# LEDStrips.net
KiCad netlist of a schematic drawn in Altium Designer
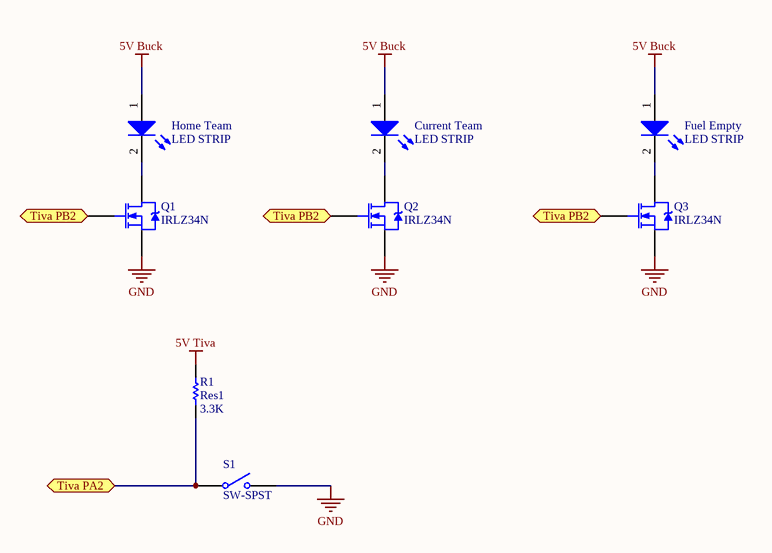
[diagram p0: LEDStrips.SchDoc]

(export (version "E")
  (design (tool "Eeschema 10.0.6"))
  (components
    (comp (ref "Current Team")
      (value "LED STRIP")
      (footprint "LED-0")
      (description "Typical INFRARED GaAs LED")
      (fields
        (field (name "MANUFACTURER") "Generic Components")
        (field (name "PUBLISHER") "Altium Hobart Technology Centre")
      )
      (libsource (lib "ME218_BaseLib") (part "LED0"))
    )
    (comp (ref "Fuel Empty")
      (value "LED STRIP")
      (footprint "LED-0")
      (description "Typical INFRARED GaAs LED")
      (fields
        (field (name "MANUFACTURER") "Generic Components")
        (field (name "PUBLISHER") "Altium Hobart Technology Centre")
      )
      (libsource (lib "ME218_BaseLib") (part "LED0"))
    )
    (comp (ref "Home Team")
      (value "LED STRIP")
      (footprint "LED-0")
      (description "Typical INFRARED GaAs LED")
      (fields
        (field (name "MANUFACTURER") "Generic Components")
        (field (name "PUBLISHER") "Altium Hobart Technology Centre")
      )
      (libsource (lib "ME218_BaseLib") (part "LED0"))
    )
    (comp (ref "Q1")
      (value "IRLZ34N")
      (footprint "SFM-T3/A4.7V")
      (description "N-Channel Power MOSFET")
      (fields (field (name "MANUFACTURER") "Generic Components"))
      (libsource (lib "ME218_BaseLib") (part "NMOS-2"))
    )
    (comp (ref "Q2")
      (value "IRLZ34N")
      (footprint "SFM-T3/A4.7V")
      (description "N-Channel Power MOSFET")
      (fields (field (name "MANUFACTURER") "Generic Components"))
      (libsource (lib "ME218_BaseLib") (part "NMOS-2"))
    )
    (comp (ref "Q3")
      (value "IRLZ34N")
      (footprint "SFM-T3/A4.7V")
      (description "N-Channel Power MOSFET")
      (fields (field (name "MANUFACTURER") "Generic Components"))
      (libsource (lib "ME218_BaseLib") (part "NMOS-2"))
    )
    (comp (ref "R1")
      (value "Res1")
      (footprint "AXIAL-0.3")
      (description "Resistor")
      (fields
        (field (name "MANUFACTURER") "Generic Components")
        (field (name "ALTIUM_VALUE") "3.3K")
        (field (name "PUBLISHER") "Altium Hobart Technology Centre")
      )
      (libsource (lib "ME218_BaseLib") (part "Res1"))
    )
    (comp (ref "S1")
      (value "SW-SPST")
      (footprint "SPST-2")
      (description "Single-Pole, Single-Throw Switch")
      (fields (field (name "MANUFACTURER") "Generic Components"))
      (libsource (lib "ME218_BaseLib") (part "SW-SPST"))
    )
  )
  (nets
    (net (code "1") (name "/Tiva PA2") (class "Default")
      (node (ref "R1") (pin "1") (pinfunction "1_1") (pintype "passive"))
      (node (ref "S1") (pin "1") (pinfunction "COMMON_1") (pintype "passive"))
    )
    (net (code "2") (name "/Tiva PB2") (class "Default")
      (node (ref "Q1") (pin "1") (pinfunction "G_1") (pintype "passive"))
      (node (ref "Q2") (pin "1") (pinfunction "G_1") (pintype "passive"))
      (node (ref "Q3") (pin "1") (pinfunction "G_1") (pintype "passive"))
    )
    (net (code "3") (name "5V Buck") (class "Default")
      (node (ref "Current Team") (pin "1") (pinfunction "A_1") (pintype "passive"))
      (node (ref "Fuel Empty") (pin "1") (pinfunction "A_1") (pintype "passive"))
      (node (ref "Home Team") (pin "1") (pinfunction "A_1") (pintype "passive"))
    )
    (net (code "4") (name "5V Tiva") (class "Default")
      (node (ref "R1") (pin "2") (pinfunction "2_2") (pintype "passive"))
    )
    (net (code "5") (name "GND") (class "Default")
      (node (ref "Q1") (pin "3") (pinfunction "S_3") (pintype "passive"))
      (node (ref "Q2") (pin "3") (pinfunction "S_3") (pintype "passive"))
      (node (ref "Q3") (pin "3") (pinfunction "S_3") (pintype "passive"))
      (node (ref "S1") (pin "2") (pinfunction "NO_2") (pintype "passive"))
    )
    (net (code "6") (name "Net-(Current Team-K)") (class "Default")
      (node (ref "Current Team") (pin "2") (pinfunction "K_2") (pintype "passive"))
      (node (ref "Q2") (pin "2") (pinfunction "D_2") (pintype "passive"))
    )
    (net (code "7") (name "Net-(Fuel Empty-K)") (class "Default")
      (node (ref "Fuel Empty") (pin "2") (pinfunction "K_2") (pintype "passive"))
      (node (ref "Q3") (pin "2") (pinfunction "D_2") (pintype "passive"))
    )
    (net (code "8") (name "Net-(Home Team-K)") (class "Default")
      (node (ref "Home Team") (pin "2") (pinfunction "K_2") (pintype "passive"))
      (node (ref "Q1") (pin "2") (pinfunction "D_2") (pintype "passive"))
    )
  )
)
